# diffamp.net
KiCad netlist of a schematic drawn in EAGLE
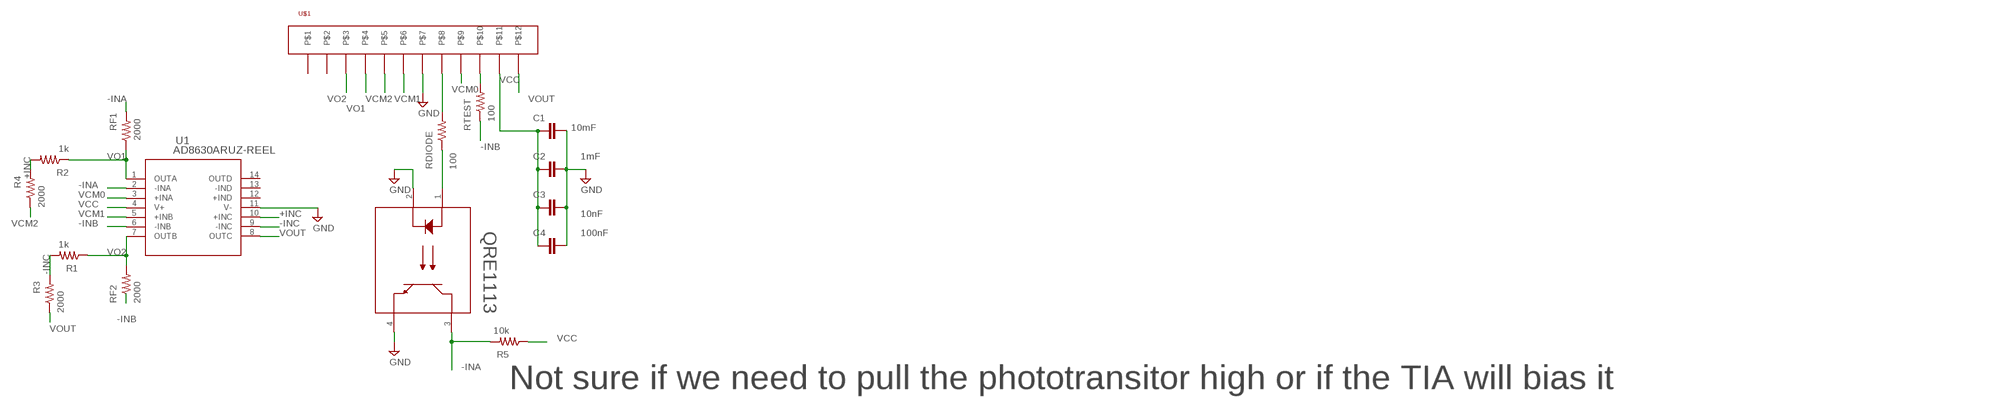
[diagram p0: schematic, sheet 1]

(export (version "E")
  (design (tool "Eeschema 10.0.6"))
  (components
    (comp (ref "C1")
      (value "10mF")
      (footprint "eagle-import:0402-CAP")
      (libsource (lib "eagle-import") (part "CAP0402-CAP"))
    )
    (comp (ref "C2")
      (value "1mF")
      (footprint "eagle-import:0402-CAP")
      (libsource (lib "eagle-import") (part "CAP0402-CAP"))
    )
    (comp (ref "C3")
      (value "10nF")
      (footprint "eagle-import:0402-CAP")
      (libsource (lib "eagle-import") (part "CAP0402-CAP"))
    )
    (comp (ref "C4")
      (value "100nF")
      (footprint "eagle-import:0402-CAP")
      (libsource (lib "eagle-import") (part "CAP0402-CAP"))
    )
    (comp (ref "Q1")
      (value "QRE1113")
      (footprint "eagle-import:DIP4_100AQ_ONS")
      (fields (field (name "COPYRIGHT") "Copyright (C) 2018 Accelerated Designs. All rights reserved"))
      (libsource (lib "eagle-import") (part "QRE1113"))
    )
    (comp (ref "R1")
      (value "1k")
      (footprint "eagle-import:R0603")
      (fields (field (name "MANUFACTURER") "Rohm Semiconductor"))
      (libsource (lib "eagle-import") (part "R-US_R0603"))
    )
    (comp (ref "R2")
      (value "1k")
      (footprint "eagle-import:R0603")
      (fields (field (name "MANUFACTURER") "Rohm Semiconductor"))
      (libsource (lib "eagle-import") (part "R-US_R0603"))
    )
    (comp (ref "R3")
      (value "2000")
      (footprint "eagle-import:R0603")
      (fields (field (name "MANUFACTURER") "Rohm Semiconductor"))
      (libsource (lib "eagle-import") (part "R-US_R0603"))
    )
    (comp (ref "R4")
      (value "2000")
      (footprint "eagle-import:R0603")
      (fields (field (name "MANUFACTURER") "Rohm Semiconductor"))
      (libsource (lib "eagle-import") (part "R-US_R0603"))
    )
    (comp (ref "R5")
      (value "10k")
      (footprint "eagle-import:R0603")
      (fields (field (name "MANUFACTURER") "Rohm Semiconductor"))
      (libsource (lib "eagle-import") (part "R-US_R0603"))
    )
    (comp (ref "RDIODE")
      (value "100")
      (footprint "eagle-import:R0603")
      (fields (field (name "MANUFACTURER") "Rohm Semiconductor"))
      (libsource (lib "eagle-import") (part "R-US_R0603"))
    )
    (comp (ref "RF1")
      (value "2000")
      (footprint "eagle-import:R0603")
      (fields (field (name "MANUFACTURER") "Rohm Semiconductor"))
      (libsource (lib "eagle-import") (part "R-US_R0603"))
    )
    (comp (ref "RF2")
      (value "2000")
      (footprint "eagle-import:R0603")
      (fields (field (name "MANUFACTURER") "Rohm Semiconductor"))
      (libsource (lib "eagle-import") (part "R-US_R0603"))
    )
    (comp (ref "RTEST")
      (value "100")
      (footprint "eagle-import:R0603")
      (fields (field (name "MANUFACTURER") "Rohm Semiconductor"))
      (libsource (lib "eagle-import") (part "R-US_R0603"))
    )
    (comp (ref "U$1")
      (value "12PIN")
      (footprint "eagle-import:12PIN")
      (libsource (lib "eagle-import") (part "12PIN"))
    )
    (comp (ref "U1")
      (value "AD8630ARUZ-REEL")
      (footprint "eagle-import:RU_14_ADI")
      (fields (field (name "COPYRIGHT") "Copyright (C) 2016 Accelerated Designs. All rights reserved"))
      (libsource (lib "eagle-import") (part "AD8630ARUZ-REEL"))
    )
  )
  (nets
    (net (code "1") (name "/+INC") (class "Default")
      (node (ref "R2") (pin "2") (pinfunction "2_2") (pintype "passive"))
      (node (ref "R4") (pin "2") (pinfunction "2_2") (pintype "passive"))
      (node (ref "U1") (pin "10") (pinfunction "+INC_10") (pintype "input"))
    )
    (net (code "2") (name "/-INA") (class "Default")
      (node (ref "Q1") (pin "3") (pinfunction "3_3") (pintype "passive"))
      (node (ref "R5") (pin "2") (pinfunction "2_2") (pintype "passive"))
      (node (ref "RF1") (pin "2") (pinfunction "2_2") (pintype "passive"))
      (node (ref "U1") (pin "2") (pinfunction "-INA_2") (pintype "input"))
    )
    (net (code "3") (name "/-INB") (class "Default")
      (node (ref "RF2") (pin "1") (pinfunction "1_1") (pintype "passive"))
      (node (ref "RTEST") (pin "1") (pinfunction "1_1") (pintype "passive"))
      (node (ref "U1") (pin "6") (pinfunction "-INB_6") (pintype "input"))
    )
    (net (code "4") (name "/-INC") (class "Default")
      (node (ref "R1") (pin "2") (pinfunction "2_2") (pintype "passive"))
      (node (ref "R3") (pin "2") (pinfunction "2_2") (pintype "passive"))
      (node (ref "U1") (pin "9") (pinfunction "-INC_9") (pintype "input"))
    )
    (net (code "5") (name "/VCC") (class "Default")
      (node (ref "C1") (pin "1") (pinfunction "1_1") (pintype "passive"))
      (node (ref "C2") (pin "1") (pinfunction "1_1") (pintype "passive"))
      (node (ref "C3") (pin "1") (pinfunction "1_1") (pintype "passive"))
      (node (ref "C4") (pin "1") (pinfunction "1_1") (pintype "passive"))
      (node (ref "R5") (pin "1") (pinfunction "1_1") (pintype "passive"))
      (node (ref "U$1") (pin "P$11") (pinfunction "P$11_P$11") (pintype "bidirectional"))
      (node (ref "U1") (pin "4") (pinfunction "V+_4") (pintype "power_in"))
    )
    (net (code "6") (name "/VCM0") (class "Default")
      (node (ref "U$1") (pin "P$9") (pinfunction "P$9_P$9") (pintype "bidirectional"))
      (node (ref "U1") (pin "3") (pinfunction "+INA_3") (pintype "input"))
    )
    (net (code "7") (name "/VCM1") (class "Default")
      (node (ref "U$1") (pin "P$6") (pinfunction "P$6_P$6") (pintype "bidirectional"))
      (node (ref "U1") (pin "5") (pinfunction "+INB_5") (pintype "input"))
    )
    (net (code "8") (name "/VCM2") (class "Default")
      (node (ref "R4") (pin "1") (pinfunction "1_1") (pintype "passive"))
      (node (ref "U$1") (pin "P$5") (pinfunction "P$5_P$5") (pintype "bidirectional"))
    )
    (net (code "9") (name "/VO1") (class "Default")
      (node (ref "R2") (pin "1") (pinfunction "1_1") (pintype "passive"))
      (node (ref "RF1") (pin "1") (pinfunction "1_1") (pintype "passive"))
      (node (ref "U$1") (pin "P$4") (pinfunction "P$4_P$4") (pintype "bidirectional"))
      (node (ref "U1") (pin "1") (pinfunction "OUTA_1") (pintype "output"))
    )
    (net (code "10") (name "/VO2") (class "Default")
      (node (ref "R1") (pin "1") (pinfunction "1_1") (pintype "passive"))
      (node (ref "RF2") (pin "2") (pinfunction "2_2") (pintype "passive"))
      (node (ref "U$1") (pin "P$3") (pinfunction "P$3_P$3") (pintype "bidirectional"))
      (node (ref "U1") (pin "7") (pinfunction "OUTB_7") (pintype "output"))
    )
    (net (code "11") (name "/VOUT") (class "Default")
      (node (ref "R3") (pin "1") (pinfunction "1_1") (pintype "passive"))
      (node (ref "U$1") (pin "P$12") (pinfunction "P$12_P$12") (pintype "bidirectional"))
      (node (ref "U1") (pin "8") (pinfunction "OUTC_8") (pintype "output"))
    )
    (net (code "12") (name "GND") (class "Default")
      (node (ref "C1") (pin "2") (pinfunction "2_2") (pintype "passive"))
      (node (ref "C2") (pin "2") (pinfunction "2_2") (pintype "passive"))
      (node (ref "C3") (pin "2") (pinfunction "2_2") (pintype "passive"))
      (node (ref "C4") (pin "2") (pinfunction "2_2") (pintype "passive"))
      (node (ref "Q1") (pin "2") (pinfunction "2_2") (pintype "passive"))
      (node (ref "Q1") (pin "4") (pinfunction "4_4") (pintype "passive"))
      (node (ref "U$1") (pin "P$7") (pinfunction "P$7_P$7") (pintype "bidirectional"))
      (node (ref "U1") (pin "11") (pinfunction "V-_11") (pintype "power_in"))
    )
    (net (code "13") (name "Net-(Q1-Pad1)") (class "Default")
      (node (ref "Q1") (pin "1") (pinfunction "1_1") (pintype "passive"))
      (node (ref "RDIODE") (pin "1") (pinfunction "1_1") (pintype "passive"))
    )
    (net (code "14") (name "Net-(RDIODE-Pad2)") (class "Default")
      (node (ref "RDIODE") (pin "2") (pinfunction "2_2") (pintype "passive"))
      (node (ref "U$1") (pin "P$8") (pinfunction "P$8_P$8") (pintype "bidirectional"))
    )
    (net (code "15") (name "Net-(RTEST-Pad2)") (class "Default")
      (node (ref "RTEST") (pin "2") (pinfunction "2_2") (pintype "passive"))
      (node (ref "U$1") (pin "P$10") (pinfunction "P$10_P$10") (pintype "bidirectional"))
    )
    (net (code "16") (name "unconnected-(U$1-PadP$1)") (class "Default")
      (node (ref "U$1") (pin "P$1") (pinfunction "P$1_P$1") (pintype "bidirectional"))
    )
    (net (code "17") (name "unconnected-(U$1-PadP$2)") (class "Default")
      (node (ref "U$1") (pin "P$2") (pinfunction "P$2_P$2") (pintype "bidirectional"))
    )
    (net (code "18") (name "unconnected-(U1-+IND-Pad12)") (class "Default")
      (node (ref "U1") (pin "12") (pinfunction "+IND_12") (pintype "input"))
    )
    (net (code "19") (name "unconnected-(U1--IND-Pad13)") (class "Default")
      (node (ref "U1") (pin "13") (pinfunction "-IND_13") (pintype "input"))
    )
    (net (code "20") (name "unconnected-(U1-OUTD-Pad14)") (class "Default")
      (node (ref "U1") (pin "14") (pinfunction "OUTD_14") (pintype "output"))
    )
  )
)
